# Sheet1.net
KiCad netlist of a schematic drawn in Altium Designer
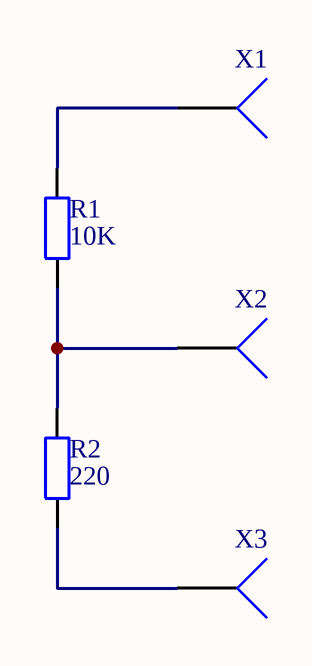
[diagram p0: Sheet1.SchDoc]

(export (version "E")
  (design (tool "Eeschema 10.0.6"))
  (components
    (comp (ref "R1")
      (value "10K")
      (footprint "_1206")
      (description "Resistor")
      (fields (field (name "MANUFACTURER") "Generic Components") (field (name "PUBLISHER") "Altium Limited"))
      (libsource (lib "Miscellaneous Devices") (part "Res2"))
    )
    (comp (ref "R2")
      (value "220")
      (footprint "_1206")
      (description "Resistor")
      (fields (field (name "MANUFACTURER") "Generic Components") (field (name "PUBLISHER") "Altium Limited"))
      (libsource (lib "Miscellaneous Devices") (part "Res2"))
    )
    (comp (ref "X1")
      (value "~")
      (footprint "PIN1")
      (description "Socket")
      (fields (field (name "MANUFACTURER") "Generic Components") (field (name "PUBLISHER") "Altium Limited"))
      (libsource (lib "Miscellaneous Connectors") (part "Socket"))
    )
    (comp (ref "X2")
      (value "~")
      (footprint "PIN1")
      (description "Socket")
      (fields (field (name "MANUFACTURER") "Generic Components") (field (name "PUBLISHER") "Altium Limited"))
      (libsource (lib "Miscellaneous Connectors") (part "Socket"))
    )
    (comp (ref "X3")
      (value "~")
      (footprint "PIN1")
      (description "Socket")
      (fields (field (name "MANUFACTURER") "Generic Components") (field (name "PUBLISHER") "Altium Limited"))
      (libsource (lib "Miscellaneous Connectors") (part "Socket"))
    )
  )
  (nets
    (net (code "1") (name "Net-(R1-Pad1)") (class "Default")
      (node (ref "R1") (pin "1") (pinfunction "1_1") (pintype "passive"))
      (node (ref "R2") (pin "2") (pinfunction "2_2") (pintype "passive"))
      (node (ref "X2") (pin "1") (pinfunction "1_1") (pintype "passive"))
    )
    (net (code "2") (name "Net-(R1-Pad2)") (class "Default")
      (node (ref "R1") (pin "2") (pinfunction "2_2") (pintype "passive"))
      (node (ref "X1") (pin "1") (pinfunction "1_1") (pintype "passive"))
    )
    (net (code "3") (name "Net-(R2-Pad1)") (class "Default")
      (node (ref "R2") (pin "1") (pinfunction "1_1") (pintype "passive"))
      (node (ref "X3") (pin "1") (pinfunction "1_1") (pintype "passive"))
    )
  )
)
